# schematic.net
KiCad netlist of a schematic drawn in EAGLE
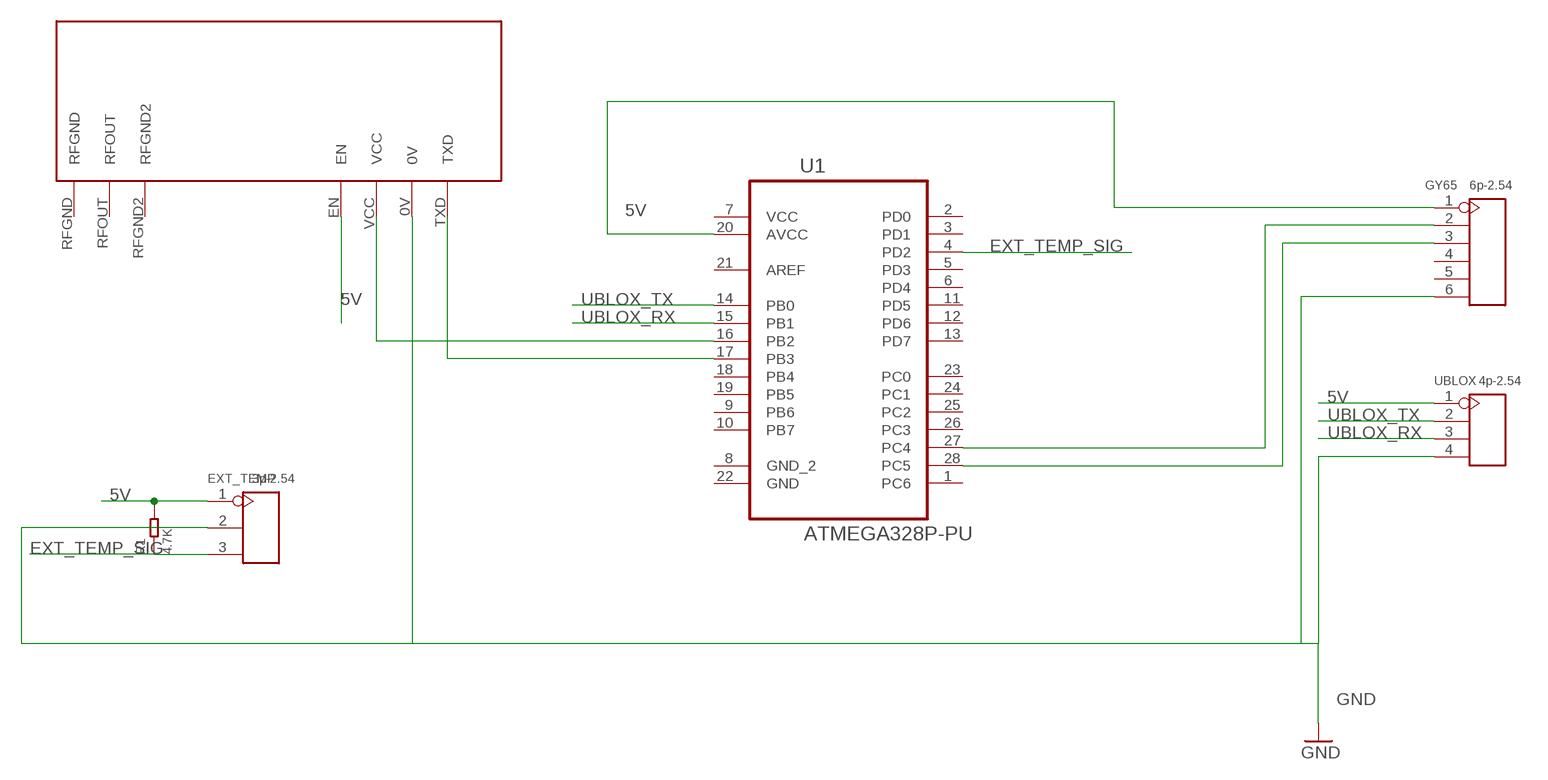
[diagram p0: schematic, sheet 1]

(export (version "E")
  (design (tool "Eeschema 10.0.6"))
  (components
    (comp (ref "EXT_TEMP")
      (value "3p-2.54")
      (footprint "eagle-import:H3-2.54")
      (libsource (lib "eagle-import") (part "DIP-BLACK-MALE-HEADER-VERT(3P-2.54)"))
    )
    (comp (ref "GY65")
      (value "6p-2.54")
      (footprint "eagle-import:H6-2.54")
      (fields (field (name "MPN") "F185-1106A1BSYC1"))
      (libsource (lib "eagle-import") (part "DIP-BLACK-FEMALE-HEADER-VERT(6P-2.54)"))
    )
    (comp (ref "R1")
      (value "4.7K")
      (footprint "eagle-import:R0402")
      (fields (field (name "MPN") "RC0402JR-074K7L"))
      (libsource (lib "eagle-import") (part "SMD-RES-4.7K-5%-1/16W(0402)"))
    )
    (comp (ref "U$1")
      (value "RADIOMETRIX-HX1")
      (footprint "eagle-import:RADIOMETRIX-HX1")
      (libsource (lib "eagle-import") (part "RADIOMETRIX-HX1"))
    )
    (comp (ref "U1")
      (value "ATMEGA328P-PU")
      (footprint "eagle-import:DIP254P762X457-28")
      (libsource (lib "eagle-import") (part "ATMEGA328P-PU"))
    )
    (comp (ref "UBLOX")
      (value "4p-2.54")
      (footprint "eagle-import:H4-2.54")
      (fields (field (name "MPN") "F185-1104A1BSYA1"))
      (libsource (lib "eagle-import") (part "DIP-BLACK-FEMALE-HEADER-VERT(4P-2.54)"))
    )
  )
  (nets
    (net (code "1") (name "/5V") (class "Default")
      (node (ref "EXT_TEMP") (pin "1") (pinfunction "P$1_1") (pintype "bidirectional"))
      (node (ref "GY65") (pin "1") (pinfunction "1_1") (pintype "bidirectional"))
      (node (ref "R1") (pin "2") (pinfunction "2_2") (pintype "passive"))
      (node (ref "U$1") (pin "EN") (pinfunction "EN_EN") (pintype "bidirectional"))
      (node (ref "U1") (pin "20") (pinfunction "AVCC_20") (pintype "power_in"))
      (node (ref "UBLOX") (pin "1") (pinfunction "P$1_1") (pintype "bidirectional"))
    )
    (net (code "2") (name "/EXT_TEMP_SIG") (class "Default")
      (node (ref "EXT_TEMP") (pin "3") (pinfunction "P$3_3") (pintype "bidirectional"))
      (node (ref "R1") (pin "1") (pinfunction "1_1") (pintype "passive"))
      (node (ref "U1") (pin "4") (pinfunction "PD2_4") (pintype "bidirectional"))
    )
    (net (code "3") (name "/UBLOX_RX") (class "Default")
      (node (ref "U1") (pin "15") (pinfunction "PB1_15") (pintype "bidirectional"))
      (node (ref "UBLOX") (pin "3") (pinfunction "P$3_3") (pintype "bidirectional"))
    )
    (net (code "4") (name "/UBLOX_TX") (class "Default")
      (node (ref "U1") (pin "14") (pinfunction "PB0_14") (pintype "bidirectional"))
      (node (ref "UBLOX") (pin "2") (pinfunction "P$2_2") (pintype "bidirectional"))
    )
    (net (code "5") (name "/VCC") (class "Default")
      (node (ref "U1") (pin "7") (pinfunction "VCC_7") (pintype "power_in"))
    )
    (net (code "6") (name "GND") (class "Default")
      (node (ref "EXT_TEMP") (pin "2") (pinfunction "P$2_2") (pintype "bidirectional"))
      (node (ref "GY65") (pin "6") (pinfunction "6_6") (pintype "bidirectional"))
      (node (ref "U$1") (pin "0V") (pinfunction "0V_0V") (pintype "bidirectional"))
      (node (ref "UBLOX") (pin "4") (pinfunction "P$4_4") (pintype "bidirectional"))
    )
    (net (code "7") (name "Net-(U1-PB2)") (class "Default")
      (node (ref "U$1") (pin "VCC") (pinfunction "VCC_VCC") (pintype "bidirectional"))
      (node (ref "U1") (pin "16") (pinfunction "PB2_16") (pintype "bidirectional"))
    )
    (net (code "8") (name "Net-(U1-PB3)") (class "Default")
      (node (ref "U$1") (pin "TXD") (pinfunction "TXD_TXD") (pintype "bidirectional"))
      (node (ref "U1") (pin "17") (pinfunction "PB3_17") (pintype "bidirectional"))
    )
    (net (code "9") (name "Net-(U1-PC4)") (class "Default")
      (node (ref "GY65") (pin "2") (pinfunction "2_2") (pintype "bidirectional"))
      (node (ref "U1") (pin "27") (pinfunction "PC4_27") (pintype "bidirectional"))
    )
    (net (code "10") (name "Net-(U1-PC5)") (class "Default")
      (node (ref "GY65") (pin "3") (pinfunction "3_3") (pintype "bidirectional"))
      (node (ref "U1") (pin "28") (pinfunction "PC5_28") (pintype "bidirectional"))
    )
    (net (code "11") (name "unconnected-(GY65-Pad4)") (class "Default")
      (node (ref "GY65") (pin "4") (pinfunction "4_4") (pintype "bidirectional"))
    )
    (net (code "12") (name "unconnected-(GY65-Pad5)") (class "Default")
      (node (ref "GY65") (pin "5") (pinfunction "5_5") (pintype "bidirectional"))
    )
    (net (code "13") (name "unconnected-(U$1-PadRFGND)") (class "Default")
      (node (ref "U$1") (pin "RFGND") (pinfunction "RFGND_RFGND") (pintype "bidirectional"))
    )
    (net (code "14") (name "unconnected-(U$1-PadRFGND2)") (class "Default")
      (node (ref "U$1") (pin "RFGND2") (pinfunction "RFGND2_RFGND2") (pintype "bidirectional"))
    )
    (net (code "15") (name "unconnected-(U$1-PadRFOUT)") (class "Default")
      (node (ref "U$1") (pin "RFOUT") (pinfunction "RFOUT_RFOUT") (pintype "bidirectional"))
    )
    (net (code "16") (name "unconnected-(U1-AREF-Pad21)") (class "Default")
      (node (ref "U1") (pin "21") (pinfunction "AREF_21") (pintype "input"))
    )
    (net (code "17") (name "unconnected-(U1-GND-Pad22)") (class "Default")
      (node (ref "U1") (pin "22") (pinfunction "GND_22") (pintype "passive"))
    )
    (net (code "18") (name "unconnected-(U1-GND_2-Pad8)") (class "Default")
      (node (ref "U1") (pin "8") (pinfunction "GND_2_8") (pintype "passive"))
    )
    (net (code "19") (name "unconnected-(U1-PB4-Pad18)") (class "Default")
      (node (ref "U1") (pin "18") (pinfunction "PB4_18") (pintype "bidirectional"))
    )
    (net (code "20") (name "unconnected-(U1-PB5-Pad19)") (class "Default")
      (node (ref "U1") (pin "19") (pinfunction "PB5_19") (pintype "bidirectional"))
    )
    (net (code "21") (name "unconnected-(U1-PB6-Pad9)") (class "Default")
      (node (ref "U1") (pin "9") (pinfunction "PB6_9") (pintype "bidirectional"))
    )
    (net (code "22") (name "unconnected-(U1-PB7-Pad10)") (class "Default")
      (node (ref "U1") (pin "10") (pinfunction "PB7_10") (pintype "bidirectional"))
    )
    (net (code "23") (name "unconnected-(U1-PC0-Pad23)") (class "Default")
      (node (ref "U1") (pin "23") (pinfunction "PC0_23") (pintype "bidirectional"))
    )
    (net (code "24") (name "unconnected-(U1-PC1-Pad24)") (class "Default")
      (node (ref "U1") (pin "24") (pinfunction "PC1_24") (pintype "bidirectional"))
    )
    (net (code "25") (name "unconnected-(U1-PC2-Pad25)") (class "Default")
      (node (ref "U1") (pin "25") (pinfunction "PC2_25") (pintype "bidirectional"))
    )
    (net (code "26") (name "unconnected-(U1-PC3-Pad26)") (class "Default")
      (node (ref "U1") (pin "26") (pinfunction "PC3_26") (pintype "bidirectional"))
    )
    (net (code "27") (name "unconnected-(U1-PC6-Pad1)") (class "Default")
      (node (ref "U1") (pin "1") (pinfunction "PC6_1") (pintype "bidirectional"))
    )
    (net (code "28") (name "unconnected-(U1-PD0-Pad2)") (class "Default")
      (node (ref "U1") (pin "2") (pinfunction "PD0_2") (pintype "bidirectional"))
    )
    (net (code "29") (name "unconnected-(U1-PD1-Pad3)") (class "Default")
      (node (ref "U1") (pin "3") (pinfunction "PD1_3") (pintype "bidirectional"))
    )
    (net (code "30") (name "unconnected-(U1-PD3-Pad5)") (class "Default")
      (node (ref "U1") (pin "5") (pinfunction "PD3_5") (pintype "bidirectional"))
    )
    (net (code "31") (name "unconnected-(U1-PD4-Pad6)") (class "Default")
      (node (ref "U1") (pin "6") (pinfunction "PD4_6") (pintype "bidirectional"))
    )
    (net (code "32") (name "unconnected-(U1-PD5-Pad11)") (class "Default")
      (node (ref "U1") (pin "11") (pinfunction "PD5_11") (pintype "bidirectional"))
    )
    (net (code "33") (name "unconnected-(U1-PD6-Pad12)") (class "Default")
      (node (ref "U1") (pin "12") (pinfunction "PD6_12") (pintype "bidirectional"))
    )
    (net (code "34") (name "unconnected-(U1-PD7-Pad13)") (class "Default")
      (node (ref "U1") (pin "13") (pinfunction "PD7_13") (pintype "bidirectional"))
    )
  )
)
